# 2016_FDP_SCHEMA.net
KiCad netlist of a schematic drawn in Altium Designer
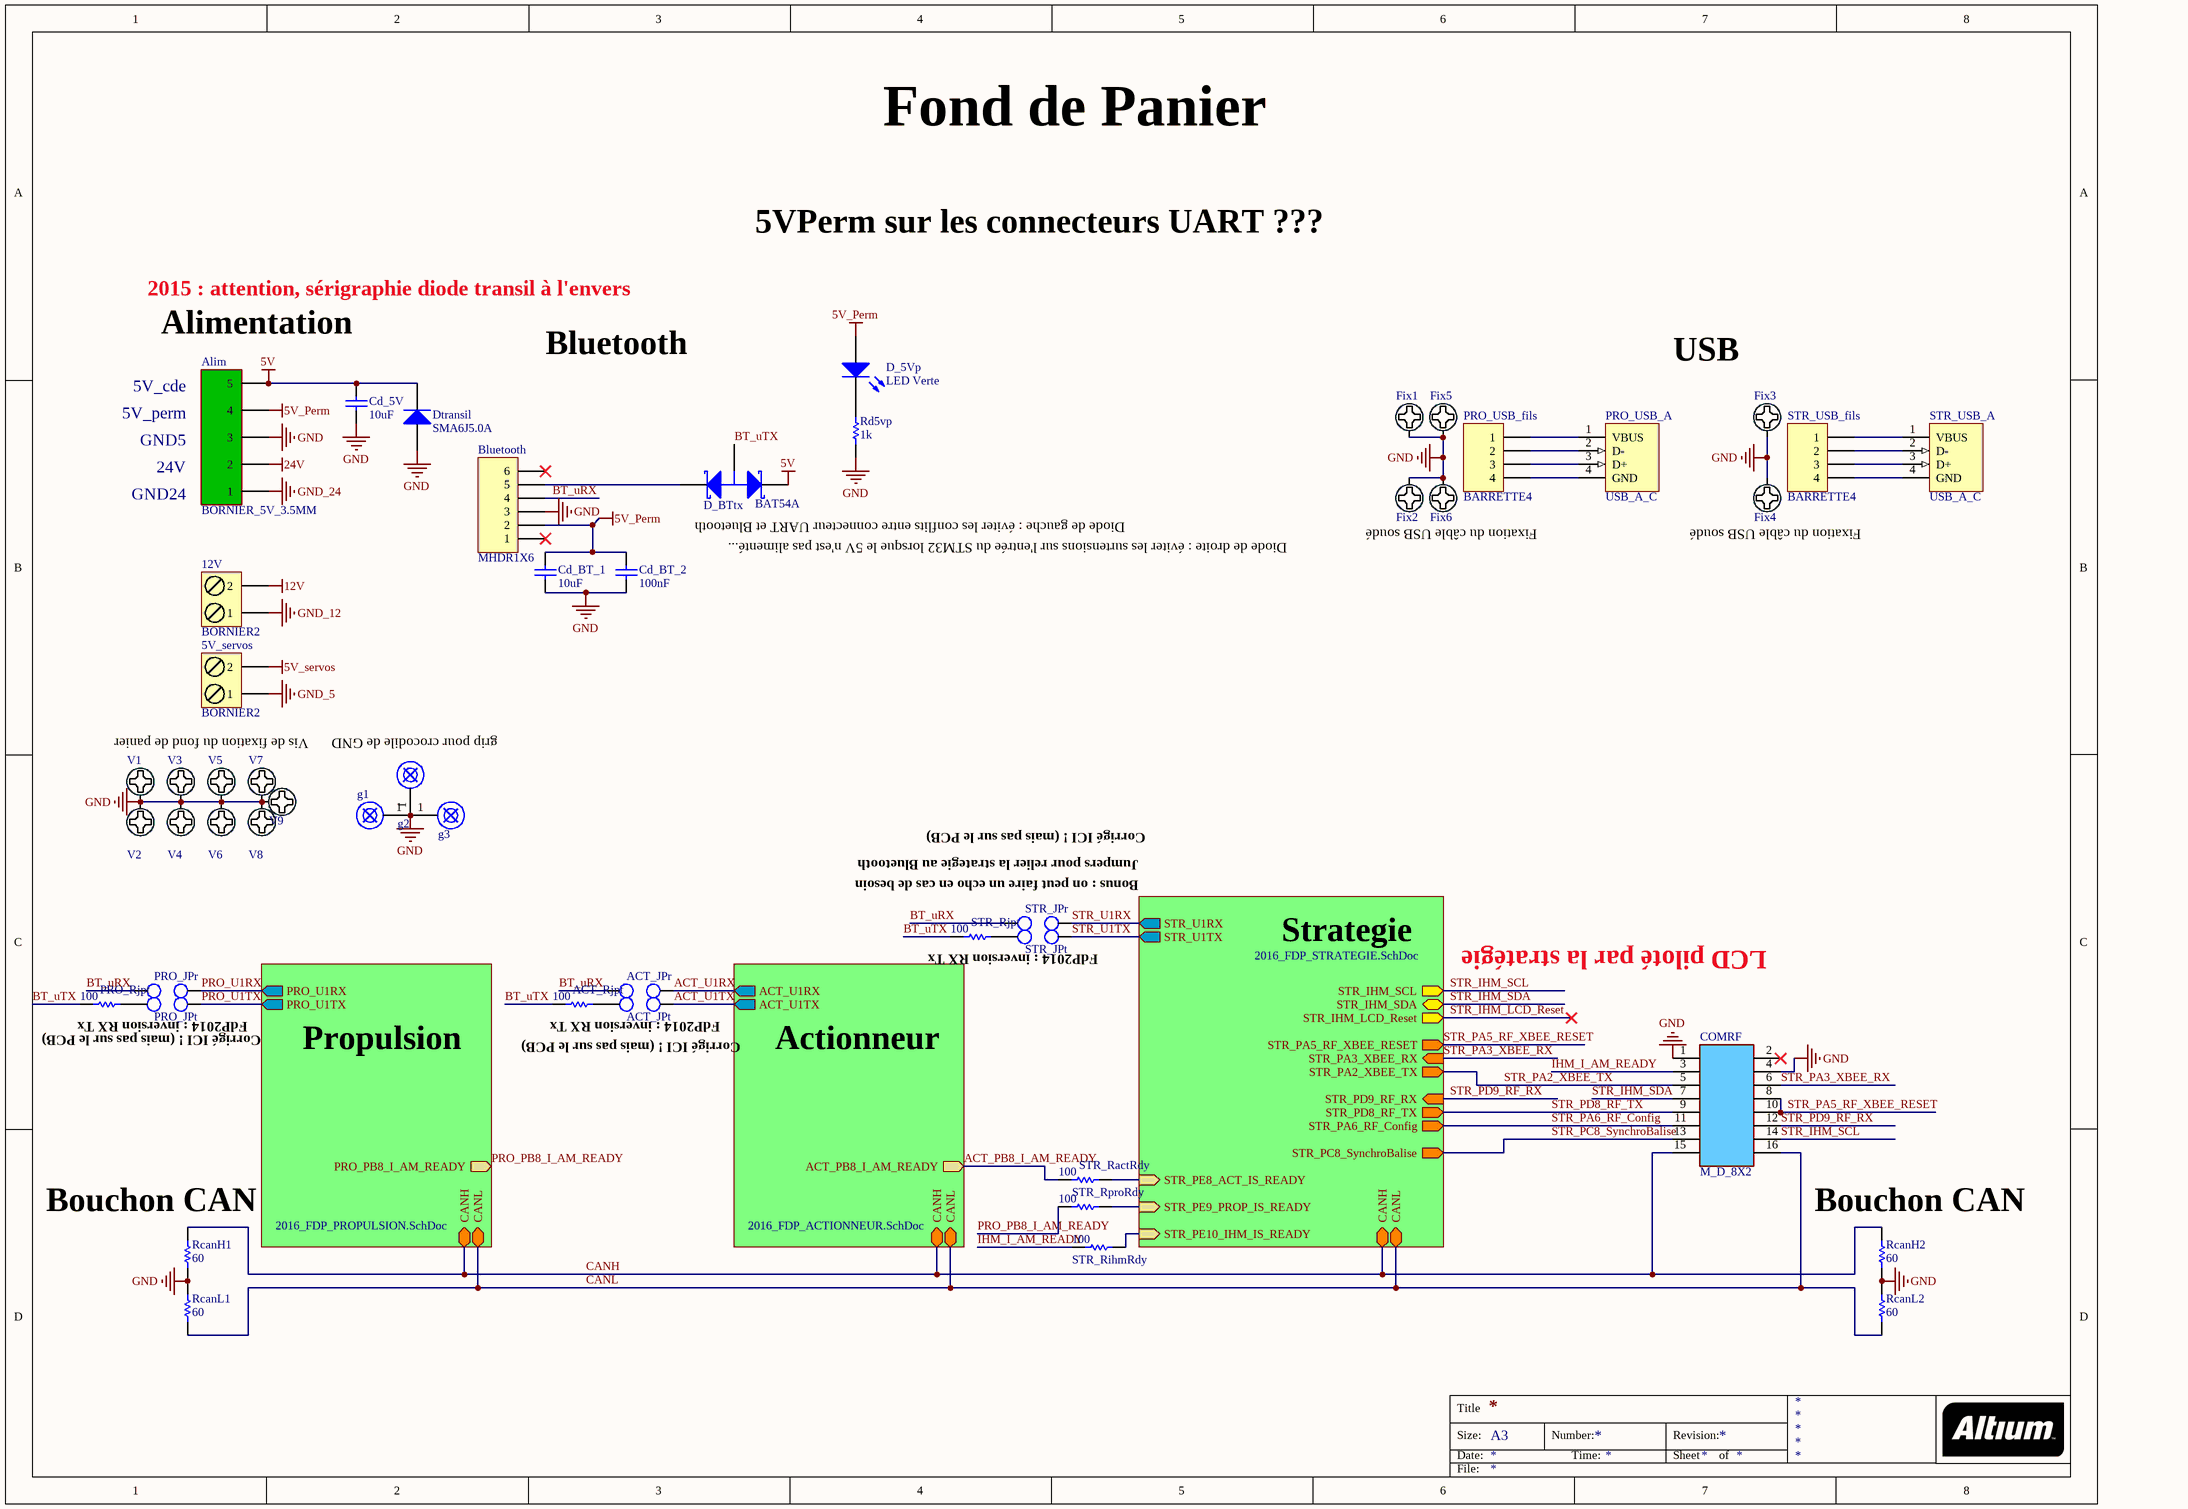
[diagram p0: 2016_FDP_SCHEMA.SchDoc]

(export (version "E")
  (design (tool "Eeschema 10.0.6"))
  (components
    (comp (ref "5V_servos")
      (value "BORNIER2")
      (footprint "BORNIER_2V_5.08MM")
      (description "Terminal blocks, 2 pins, pitch=5mm")
      (libsource (lib "Connecteur") (part "BORNIER2"))
    )
    (comp (ref "12V")
      (value "BORNIER2")
      (footprint "BORNIER_2V_5.08MM")
      (description "Terminal blocks, 2 pins, pitch=5mm")
      (libsource (lib "Connecteur") (part "BORNIER2"))
    )
    (comp (ref "ACT_JPr")
      (value "JUMPER2")
      (footprint "BARRETTE_2_M_D")
      (description "BARRETTE 2 CONTACTS 1 RANGEE MALE DROITE")
      (libsource (lib "connecteurs") (part "JUMPER2"))
    )
    (comp (ref "ACT_JPt")
      (value "JUMPER2")
      (footprint "BARRETTE_2_M_D")
      (description "BARRETTE 2 CONTACTS 1 RANGEE MALE DROITE")
      (libsource (lib "connecteurs") (part "JUMPER2"))
    )
    (comp (ref "ACT_Rjpt")
      (value "100")
      (footprint "R1206_N")
      (description "Resistor")
      (fields (field (name "PUBLISHER") "Altium Limited"))
      (libsource (lib "_ROBOT") (part "Resistor"))
    )
    (comp (ref "Alim")
      (value "BORNIER_5V_3.5MM")
      (footprint "BORNIER_5V_3.5MM_femelle_0")
      (libsource (lib "Connecteur") (part "BORNIER_5V_3.5MM"))
    )
    (comp (ref "Bluetooth")
      (value "MHDR1X6")
      (footprint "HE14_6")
      (description "Header, 6-Pin")
      (fields (field (name "PUBLISHER") "Altium Limited"))
      (libsource (lib "Miscellaneous Connectors") (part "MHDR1X6"))
    )
    (comp (ref "Cd_5V")
      (value "10uF")
      (footprint "C1206_N")
      (description "Capacitor")
      (fields (field (name "PUBLISHER") "Altium Limited"))
      (libsource (lib "_ROBOT") (part "Condensateur"))
    )
    (comp (ref "Cd_BT_1")
      (value "10uF")
      (footprint "C1206_N")
      (description "Capacitor")
      (fields (field (name "PUBLISHER") "Altium Limited"))
      (libsource (lib "_ROBOT") (part "Condensateur"))
    )
    (comp (ref "Cd_BT_2")
      (value "100nF")
      (footprint "C0805_N")
      (description "Capacitor")
      (fields (field (name "PUBLISHER") "Altium Limited"))
      (libsource (lib "_ROBOT") (part "Condensateur"))
    )
    (comp (ref "COMRF")
      (value "BARRETTE_8 CONTACTS_2 RANGEES_MALE_DROITE")
      (footprint "HE10/16_M_D_B P")
      (fields (field (name "TYPE") "M_D_8X2"))
      (libsource (lib "connecteurs") (part "BARRETTE_8 CONTACTS_2 RANGEES_MALE_DROITE"))
    )
    (comp (ref "Dtransil")
      (value "SMA6J5.0A")
      (footprint "DO214AC")
      (description "1 Amp General Purpose Rectifier")
      (fields (field (name "PUBLISHER") "Altium Limited"))
      (libsource (lib "Miscellaneous Devices") (part "Diode 1N4001"))
    )
    (comp (ref "D_5Vp")
      (value "LED Verte")
      (footprint "LED_0805")
      (description "Typical LED")
      (fields (field (name "PUBLISHER") "Altium Limited"))
      (libsource (lib "_ROBOT") (part "LED"))
    )
    (comp (ref "D_BTtx")
      (value "BAT54A")
      (footprint "SOT23-3N")
      (description "DIODE SCHOTTKY DOUBLE")
      (fields (field (name "MANUFACTURER") "ZETEX"))
      (libsource (lib "_ROBOT") (part "Diode Shottky double  BAT54A"))
    )
    (comp (ref "Fix1")
      (value "Pad_M3")
      (footprint "Point Test_D3_P1.6mm")
      (description "Vis M3 X 6mm _TORX_Tête 6mm")
      (fields (field (name "PUBLISHER") "Damien Guitton"))
      (libsource (lib "DG_Mecanique") (part "Vis M3 X 6mm _TORX_Tête 6mm"))
    )
    (comp (ref "Fix2")
      (value "Pad_M3")
      (footprint "Point Test_D3_P1.6mm")
      (description "Vis M3 X 6mm _TORX_Tête 6mm")
      (fields (field (name "PUBLISHER") "Damien Guitton"))
      (libsource (lib "DG_Mecanique") (part "Vis M3 X 6mm _TORX_Tête 6mm"))
    )
    (comp (ref "Fix3")
      (value "Pad_M3")
      (footprint "Point Test_D3_P1.6mm")
      (description "Vis M3 X 6mm _TORX_Tête 6mm")
      (fields (field (name "PUBLISHER") "Damien Guitton"))
      (libsource (lib "DG_Mecanique") (part "Vis M3 X 6mm _TORX_Tête 6mm"))
    )
    (comp (ref "Fix4")
      (value "Pad_M3")
      (footprint "Point Test_D3_P1.6mm")
      (description "Vis M3 X 6mm _TORX_Tête 6mm")
      (fields (field (name "PUBLISHER") "Damien Guitton"))
      (libsource (lib "DG_Mecanique") (part "Vis M3 X 6mm _TORX_Tête 6mm"))
    )
    (comp (ref "Fix5")
      (value "Pad_M3")
      (footprint "Point Test_D3_P1.6mm")
      (description "Vis M3 X 6mm _TORX_Tête 6mm")
      (fields (field (name "PUBLISHER") "Damien Guitton"))
      (libsource (lib "DG_Mecanique") (part "Vis M3 X 6mm _TORX_Tête 6mm"))
    )
    (comp (ref "Fix6")
      (value "Pad_M3")
      (footprint "Point Test_D3_P1.6mm")
      (description "Vis M3 X 6mm _TORX_Tête 6mm")
      (fields (field (name "PUBLISHER") "Damien Guitton"))
      (libsource (lib "DG_Mecanique") (part "Vis M3 X 6mm _TORX_Tête 6mm"))
    )
    (comp (ref "g1")
      (value "grip")
      (footprint "POINT_TEST")
      (description "POINT TEST")
      (libsource (lib "connecteurs") (part "POINT_TEST"))
    )
    (comp (ref "g2")
      (value "grip")
      (footprint "POINT_TEST")
      (description "POINT TEST")
      (libsource (lib "connecteurs") (part "POINT_TEST"))
    )
    (comp (ref "g3")
      (value "grip")
      (footprint "POINT_TEST")
      (description "POINT TEST")
      (libsource (lib "connecteurs") (part "POINT_TEST"))
    )
    (comp (ref "PRO_JPr")
      (value "JUMPER2")
      (footprint "BARRETTE_2_M_D")
      (description "BARRETTE 2 CONTACTS 1 RANGEE MALE DROITE")
      (libsource (lib "connecteurs") (part "JUMPER2"))
    )
    (comp (ref "PRO_JPt")
      (value "JUMPER2")
      (footprint "BARRETTE_2_M_D")
      (description "BARRETTE 2 CONTACTS 1 RANGEE MALE DROITE")
      (libsource (lib "connecteurs") (part "JUMPER2"))
    )
    (comp (ref "PRO_Rjpt")
      (value "100")
      (footprint "R1206_N")
      (description "Resistor")
      (fields (field (name "PUBLISHER") "Altium Limited"))
      (libsource (lib "_ROBOT") (part "Resistor"))
    )
    (comp (ref "PRO_USB_A")
      (value "USB_A_COUDEE")
      (footprint "USB_A_C")
      (description "EMBASE USB TRAVERSANTE TYPE A COUDEE")
      (fields (field (name "TYPE") "USB_A_C"))
      (libsource (lib "connecteurs") (part "USB_A_COUDEE"))
    )
    (comp (ref "PRO_USB_fils")
      (value "BARRETTE4")
      (footprint "HE14_4")
      (description "Header, 4-Pin")
      (fields (field (name "PUBLISHER") "Altium Limited"))
      (libsource (lib "Connecteur") (part "BARRETTE4"))
    )
    (comp (ref "RcanH1")
      (value "60")
      (footprint "R1206_N")
      (description "Resistor")
      (fields (field (name "PUBLISHER") "Altium Limited"))
      (libsource (lib "_ROBOT") (part "Resistor"))
    )
    (comp (ref "RcanH2")
      (value "60")
      (footprint "R1206_N")
      (description "Resistor")
      (fields (field (name "PUBLISHER") "Altium Limited"))
      (libsource (lib "_ROBOT") (part "Resistor"))
    )
    (comp (ref "RcanL1")
      (value "60")
      (footprint "R1206_N")
      (description "Resistor")
      (fields (field (name "PUBLISHER") "Altium Limited"))
      (libsource (lib "_ROBOT") (part "Resistor"))
    )
    (comp (ref "RcanL2")
      (value "60")
      (footprint "R1206_N")
      (description "Resistor")
      (fields (field (name "PUBLISHER") "Altium Limited"))
      (libsource (lib "_ROBOT") (part "Resistor"))
    )
    (comp (ref "Rd5vp")
      (value "1k")
      (footprint "R1206_N")
      (description "Resistor")
      (fields (field (name "PUBLISHER") "Altium Limited"))
      (libsource (lib "_ROBOT") (part "Resistor"))
    )
    (comp (ref "STR_JPr")
      (value "JUMPER2")
      (footprint "BARRETTE_2_M_D")
      (description "BARRETTE 2 CONTACTS 1 RANGEE MALE DROITE")
      (libsource (lib "connecteurs") (part "JUMPER2"))
    )
    (comp (ref "STR_JPt")
      (value "JUMPER2")
      (footprint "BARRETTE_2_M_D")
      (description "BARRETTE 2 CONTACTS 1 RANGEE MALE DROITE")
      (libsource (lib "connecteurs") (part "JUMPER2"))
    )
    (comp (ref "STR_RactRdy")
      (value "100")
      (footprint "R1206_N")
      (description "Resistor")
      (fields (field (name "PUBLISHER") "Altium Limited"))
      (libsource (lib "_ROBOT") (part "Resistor"))
    )
    (comp (ref "STR_RihmRdy")
      (value "100")
      (footprint "R1206_N")
      (description "Resistor")
      (fields (field (name "PUBLISHER") "Altium Limited"))
      (libsource (lib "_ROBOT") (part "Resistor"))
    )
    (comp (ref "STR_Rjpt")
      (value "100")
      (footprint "R1206_N")
      (description "Resistor")
      (fields (field (name "PUBLISHER") "Altium Limited"))
      (libsource (lib "_ROBOT") (part "Resistor"))
    )
    (comp (ref "STR_RproRdy")
      (value "100")
      (footprint "R1206_N")
      (description "Resistor")
      (fields (field (name "PUBLISHER") "Altium Limited"))
      (libsource (lib "_ROBOT") (part "Resistor"))
    )
    (comp (ref "STR_USB_A")
      (value "USB_A_COUDEE")
      (footprint "USB_A_C")
      (description "EMBASE USB TRAVERSANTE TYPE A COUDEE")
      (fields (field (name "TYPE") "USB_A_C"))
      (libsource (lib "connecteurs") (part "USB_A_COUDEE"))
    )
    (comp (ref "STR_USB_fils")
      (value "BARRETTE4")
      (footprint "HE14_4")
      (description "Header, 4-Pin")
      (fields (field (name "PUBLISHER") "Altium Limited"))
      (libsource (lib "Connecteur") (part "BARRETTE4"))
    )
    (comp (ref "V1")
      (value "Pad_M3")
      (footprint "M3x6mm Torx")
      (description "Vis M3 X 6mm _TORX_Tête 6mm")
      (fields (field (name "PUBLISHER") "Damien Guitton"))
      (libsource (lib "DG_Mecanique") (part "Vis M3 X 6mm _TORX_Tête 6mm"))
    )
    (comp (ref "V2")
      (value "Pad_M3")
      (footprint "M3x6mm Torx")
      (description "Vis M3 X 6mm _TORX_Tête 6mm")
      (fields (field (name "PUBLISHER") "Damien Guitton"))
      (libsource (lib "DG_Mecanique") (part "Vis M3 X 6mm _TORX_Tête 6mm"))
    )
    (comp (ref "V3")
      (value "Pad_M3")
      (footprint "M3x6mm Torx")
      (description "Vis M3 X 6mm _TORX_Tête 6mm")
      (fields (field (name "PUBLISHER") "Damien Guitton"))
      (libsource (lib "DG_Mecanique") (part "Vis M3 X 6mm _TORX_Tête 6mm"))
    )
    (comp (ref "V4")
      (value "Pad_M3")
      (footprint "M3x6mm Torx")
      (description "Vis M3 X 6mm _TORX_Tête 6mm")
      (fields (field (name "PUBLISHER") "Damien Guitton"))
      (libsource (lib "DG_Mecanique") (part "Vis M3 X 6mm _TORX_Tête 6mm"))
    )
    (comp (ref "V5")
      (value "Pad_M3")
      (footprint "M3x6mm Torx")
      (description "Vis M3 X 6mm _TORX_Tête 6mm")
      (fields (field (name "PUBLISHER") "Damien Guitton"))
      (libsource (lib "DG_Mecanique") (part "Vis M3 X 6mm _TORX_Tête 6mm"))
    )
    (comp (ref "V6")
      (value "Pad_M3")
      (footprint "M3x6mm Torx")
      (description "Vis M3 X 6mm _TORX_Tête 6mm")
      (fields (field (name "PUBLISHER") "Damien Guitton"))
      (libsource (lib "DG_Mecanique") (part "Vis M3 X 6mm _TORX_Tête 6mm"))
    )
    (comp (ref "V7")
      (value "Pad_M3")
      (footprint "M3x6mm Torx")
      (description "Vis M3 X 6mm _TORX_Tête 6mm")
      (fields (field (name "PUBLISHER") "Damien Guitton"))
      (libsource (lib "DG_Mecanique") (part "Vis M3 X 6mm _TORX_Tête 6mm"))
    )
    (comp (ref "V8")
      (value "Pad_M3")
      (footprint "M3x6mm Torx")
      (description "Vis M3 X 6mm _TORX_Tête 6mm")
      (fields (field (name "PUBLISHER") "Damien Guitton"))
      (libsource (lib "DG_Mecanique") (part "Vis M3 X 6mm _TORX_Tête 6mm"))
    )
    (comp (ref "V9")
      (value "Pad_M3")
      (footprint "M3x6mm Torx")
      (description "Vis M3 X 6mm _TORX_Tête 6mm")
      (fields (field (name "PUBLISHER") "Damien Guitton"))
      (libsource (lib "DG_Mecanique") (part "Vis M3 X 6mm _TORX_Tête 6mm"))
    )
  )
  (nets
    (net (code "1") (name "/ACT_PB8_I_AM_READY") (class "Default")
      (node (ref "STR_RactRdy") (pin "2") (pinfunction "2_2") (pintype "passive"))
    )
    (net (code "2") (name "/ACT_U1RX") (class "Default")
      (node (ref "ACT_JPr") (pin "2") (pinfunction "2_2") (pintype "passive"))
    )
    (net (code "3") (name "/ACT_U1TX") (class "Default")
      (node (ref "ACT_JPt") (pin "2") (pinfunction "2_2") (pintype "passive"))
    )
    (net (code "4") (name "/BT_uRX") (class "Default")
      (node (ref "ACT_JPr") (pin "1") (pinfunction "1_1") (pintype "passive"))
      (node (ref "Bluetooth") (pin "4") (pinfunction "4_4") (pintype "passive"))
      (node (ref "PRO_JPr") (pin "1") (pinfunction "1_1") (pintype "passive"))
      (node (ref "STR_JPr") (pin "1") (pinfunction "1_1") (pintype "passive"))
    )
    (net (code "5") (name "/BT_uTX") (class "Default")
      (node (ref "ACT_Rjpt") (pin "2") (pinfunction "2_2") (pintype "passive"))
      (node (ref "D_BTtx") (pin "3") (pinfunction "A_3") (pintype "passive"))
      (node (ref "PRO_Rjpt") (pin "2") (pinfunction "2_2") (pintype "passive"))
      (node (ref "STR_Rjpt") (pin "2") (pinfunction "2_2") (pintype "passive"))
    )
    (net (code "6") (name "/CANH") (class "Default")
      (node (ref "COMRF") (pin "15") (pinfunction "15_15") (pintype "passive"))
      (node (ref "RcanH1") (pin "2") (pinfunction "2_2") (pintype "passive"))
      (node (ref "RcanH2") (pin "1") (pinfunction "1_1") (pintype "passive"))
    )
    (net (code "7") (name "/CANL") (class "Default")
      (node (ref "COMRF") (pin "16") (pinfunction "16_16") (pintype "passive"))
      (node (ref "RcanL1") (pin "1") (pinfunction "1_1") (pintype "passive"))
      (node (ref "RcanL2") (pin "1") (pinfunction "1_1") (pintype "passive"))
    )
    (net (code "8") (name "/IHM_I_AM_READY") (class "Default")
      (node (ref "COMRF") (pin "3") (pinfunction "3_3") (pintype "passive"))
      (node (ref "STR_RihmRdy") (pin "2") (pinfunction "2_2") (pintype "passive"))
    )
    (net (code "9") (name "/PRO_PB8_I_AM_READY") (class "Default")
      (node (ref "STR_RproRdy") (pin "2") (pinfunction "2_2") (pintype "passive"))
    )
    (net (code "10") (name "/PRO_U1RX") (class "Default")
      (node (ref "PRO_JPr") (pin "2") (pinfunction "2_2") (pintype "passive"))
    )
    (net (code "11") (name "/PRO_U1TX") (class "Default")
      (node (ref "PRO_JPt") (pin "2") (pinfunction "2_2") (pintype "passive"))
    )
    (net (code "13") (name "/STR_IHM_SCL") (class "Default")
      (node (ref "COMRF") (pin "14") (pinfunction "14_14") (pintype "passive"))
    )
    (net (code "14") (name "/STR_IHM_SDA") (class "Default")
      (node (ref "COMRF") (pin "7") (pinfunction "7_7") (pintype "passive"))
    )
    (net (code "15") (name "/STR_PA2_XBEE_TX") (class "Default")
      (node (ref "COMRF") (pin "5") (pinfunction "5_5") (pintype "passive"))
    )
    (net (code "16") (name "/STR_PA3_XBEE_RX") (class "Default")
      (node (ref "COMRF") (pin "6") (pinfunction "6_6") (pintype "passive"))
    )
    (net (code "17") (name "/STR_PA5_RF_XBEE_RESET") (class "Default")
      (node (ref "COMRF") (pin "10") (pinfunction "10_10") (pintype "passive"))
      (node (ref "COMRF") (pin "8") (pinfunction "8_8") (pintype "passive"))
    )
    (net (code "18") (name "/STR_PA6_RF_Config") (class "Default")
      (node (ref "COMRF") (pin "11") (pinfunction "11_11") (pintype "passive"))
    )
    (net (code "19") (name "/STR_PC8_SynchroBalise") (class "Default")
      (node (ref "COMRF") (pin "13") (pinfunction "13_13") (pintype "passive"))
    )
    (net (code "20") (name "/STR_PD8_RF_TX") (class "Default")
      (node (ref "COMRF") (pin "9") (pinfunction "9_9") (pintype "passive"))
    )
    (net (code "21") (name "/STR_PD9_RF_RX") (class "Default")
      (node (ref "COMRF") (pin "12") (pinfunction "12_12") (pintype "passive"))
    )
    (net (code "22") (name "/STR_PE8_ACT_IS_READY") (class "Default")
      (node (ref "STR_RactRdy") (pin "1") (pinfunction "1_1") (pintype "passive"))
    )
    (net (code "23") (name "/STR_PE9_PROP_IS_READY") (class "Default")
      (node (ref "STR_RproRdy") (pin "1") (pinfunction "1_1") (pintype "passive"))
    )
    (net (code "24") (name "/STR_PE10_IHM_IS_READY") (class "Default")
      (node (ref "STR_RihmRdy") (pin "1") (pinfunction "1_1") (pintype "passive"))
    )
    (net (code "25") (name "/STR_U1RX") (class "Default")
      (node (ref "STR_JPr") (pin "2") (pinfunction "2_2") (pintype "passive"))
    )
    (net (code "26") (name "/STR_U1TX") (class "Default")
      (node (ref "STR_JPt") (pin "2") (pinfunction "2_2") (pintype "passive"))
    )
    (net (code "27") (name "5V") (class "Default")
      (node (ref "Alim") (pin "5") (pinfunction "5_5") (pintype "passive"))
      (node (ref "Cd_5V") (pin "2") (pinfunction "2_2") (pintype "passive"))
      (node (ref "D_BTtx") (pin "2") (pinfunction "K2_2") (pintype "passive"))
      (node (ref "Dtransil") (pin "2") (pinfunction "K_2") (pintype "passive"))
    )
    (net (code "28") (name "5V_Perm") (class "Default")
      (node (ref "Alim") (pin "4") (pinfunction "4_4") (pintype "passive"))
      (node (ref "Bluetooth") (pin "2") (pinfunction "2_2") (pintype "passive"))
      (node (ref "Cd_BT_1") (pin "2") (pinfunction "2_2") (pintype "passive"))
      (node (ref "Cd_BT_2") (pin "2") (pinfunction "2_2") (pintype "passive"))
      (node (ref "D_5Vp") (pin "1") (pinfunction "A_1") (pintype "passive"))
    )
    (net (code "29") (name "5V_servos") (class "Default")
      (node (ref "5V_servos") (pin "2") (pinfunction "2_2") (pintype "passive"))
    )
    (net (code "30") (name "12V") (class "Default")
      (node (ref "12V") (pin "2") (pinfunction "2_2") (pintype "passive"))
    )
    (net (code "31") (name "24V") (class "Default")
      (node (ref "Alim") (pin "2") (pinfunction "2_2") (pintype "passive"))
    )
    (net (code "32") (name "GND") (class "Default")
      (node (ref "Alim") (pin "3") (pinfunction "3_3") (pintype "passive"))
      (node (ref "Bluetooth") (pin "3") (pinfunction "3_3") (pintype "passive"))
      (node (ref "COMRF") (pin "1") (pinfunction "1_1") (pintype "passive"))
      (node (ref "COMRF") (pin "4") (pinfunction "4_4") (pintype "passive"))
      (node (ref "Cd_5V") (pin "1") (pinfunction "1_1") (pintype "passive"))
      (node (ref "Cd_BT_1") (pin "1") (pinfunction "1_1") (pintype "passive"))
      (node (ref "Cd_BT_2") (pin "1") (pinfunction "1_1") (pintype "passive"))
      (node (ref "Dtransil") (pin "1") (pinfunction "A_1") (pintype "passive"))
      (node (ref "Fix1") (pin "1") (pinfunction "1_1") (pintype "passive"))
      (node (ref "Fix2") (pin "1") (pinfunction "1_1") (pintype "passive"))
      (node (ref "Fix3") (pin "1") (pinfunction "1_1") (pintype "passive"))
      (node (ref "Fix4") (pin "1") (pinfunction "1_1") (pintype "passive"))
      (node (ref "Fix5") (pin "1") (pinfunction "1_1") (pintype "passive"))
      (node (ref "Fix6") (pin "1") (pinfunction "1_1") (pintype "passive"))
      (node (ref "RcanH1") (pin "1") (pinfunction "1_1") (pintype "passive"))
      (node (ref "RcanH2") (pin "2") (pinfunction "2_2") (pintype "passive"))
      (node (ref "RcanL1") (pin "2") (pinfunction "2_2") (pintype "passive"))
      (node (ref "RcanL2") (pin "2") (pinfunction "2_2") (pintype "passive"))
      (node (ref "Rd5vp") (pin "2") (pinfunction "2_2") (pintype "passive"))
      (node (ref "V1") (pin "1") (pinfunction "1_1") (pintype "passive"))
      (node (ref "V2") (pin "1") (pinfunction "1_1") (pintype "passive"))
      (node (ref "V3") (pin "1") (pinfunction "1_1") (pintype "passive"))
      (node (ref "V4") (pin "1") (pinfunction "1_1") (pintype "passive"))
      (node (ref "V5") (pin "1") (pinfunction "1_1") (pintype "passive"))
      (node (ref "V6") (pin "1") (pinfunction "1_1") (pintype "passive"))
      (node (ref "V7") (pin "1") (pinfunction "1_1") (pintype "passive"))
      (node (ref "V8") (pin "1") (pinfunction "1_1") (pintype "passive"))
      (node (ref "V9") (pin "1") (pinfunction "1_1") (pintype "passive"))
      (node (ref "g1") (pin "1") (pinfunction "3_1") (pintype "passive"))
      (node (ref "g2") (pin "1") (pinfunction "3_1") (pintype "passive"))
      (node (ref "g3") (pin "1") (pinfunction "3_1") (pintype "passive"))
    )
    (net (code "33") (name "GND_5") (class "Default")
      (node (ref "5V_servos") (pin "1") (pinfunction "1_1") (pintype "passive"))
    )
    (net (code "34") (name "GND_12") (class "Default")
      (node (ref "12V") (pin "1") (pinfunction "1_1") (pintype "passive"))
    )
    (net (code "35") (name "GND_24") (class "Default")
      (node (ref "Alim") (pin "1") (pinfunction "1_1") (pintype "passive"))
    )
    (net (code "36") (name "Net-(ACT_JPt-Pad1)") (class "Default")
      (node (ref "ACT_JPt") (pin "1") (pinfunction "1_1") (pintype "passive"))
      (node (ref "ACT_Rjpt") (pin "1") (pinfunction "1_1") (pintype "passive"))
    )
    (net (code "37") (name "Net-(D_5Vp-K)") (class "Default")
      (node (ref "D_5Vp") (pin "2") (pinfunction "K_2") (pintype "passive"))
      (node (ref "Rd5vp") (pin "1") (pinfunction "1_1") (pintype "passive"))
    )
    (net (code "38") (name "Net-(D_BTtx-K1)") (class "Default")
      (node (ref "Bluetooth") (pin "5") (pinfunction "5_5") (pintype "passive"))
      (node (ref "D_BTtx") (pin "1") (pinfunction "K1_1") (pintype "passive"))
    )
    (net (code "39") (name "Net-(PRO_JPt-Pad1)") (class "Default")
      (node (ref "PRO_JPt") (pin "1") (pinfunction "1_1") (pintype "passive"))
      (node (ref "PRO_Rjpt") (pin "1") (pinfunction "1_1") (pintype "passive"))
    )
    (net (code "40") (name "Net-(PRO_USB_A-D+)") (class "Default")
      (node (ref "PRO_USB_A") (pin "3") (pinfunction "D+_3") (pintype "input"))
      (node (ref "PRO_USB_fils") (pin "3") (pinfunction "3_3") (pintype "passive"))
    )
    (net (code "41") (name "Net-(PRO_USB_A-D-)") (class "Default")
      (node (ref "PRO_USB_A") (pin "2") (pinfunction "D-_2") (pintype "input"))
      (node (ref "PRO_USB_fils") (pin "2") (pinfunction "2_2") (pintype "passive"))
    )
    (net (code "42") (name "Net-(PRO_USB_A-GND)") (class "Default")
      (node (ref "PRO_USB_A") (pin "4") (pinfunction "GND_4") (pintype "power_in"))
      (node (ref "PRO_USB_fils") (pin "4") (pinfunction "4_4") (pintype "passive"))
    )
    (net (code "43") (name "Net-(PRO_USB_A-VBUS)") (class "Default")
      (node (ref "PRO_USB_A") (pin "1") (pinfunction "VBUS_1") (pintype "power_in"))
      (node (ref "PRO_USB_fils") (pin "1") (pinfunction "1_1") (pintype "passive"))
    )
    (net (code "44") (name "Net-(STR_JPt-Pad1)") (class "Default")
      (node (ref "STR_JPt") (pin "1") (pinfunction "1_1") (pintype "passive"))
      (node (ref "STR_Rjpt") (pin "1") (pinfunction "1_1") (pintype "passive"))
    )
    (net (code "45") (name "Net-(STR_USB_A-D+)") (class "Default")
      (node (ref "STR_USB_A") (pin "3") (pinfunction "D+_3") (pintype "input"))
      (node (ref "STR_USB_fils") (pin "3") (pinfunction "3_3") (pintype "passive"))
    )
    (net (code "46") (name "Net-(STR_USB_A-D-)") (class "Default")
      (node (ref "STR_USB_A") (pin "2") (pinfunction "D-_2") (pintype "input"))
      (node (ref "STR_USB_fils") (pin "2") (pinfunction "2_2") (pintype "passive"))
    )
    (net (code "47") (name "Net-(STR_USB_A-GND)") (class "Default")
      (node (ref "STR_USB_A") (pin "4") (pinfunction "GND_4") (pintype "power_in"))
      (node (ref "STR_USB_fils") (pin "4") (pinfunction "4_4") (pintype "passive"))
    )
    (net (code "48") (name "Net-(STR_USB_A-VBUS)") (class "Default")
      (node (ref "STR_USB_A") (pin "1") (pinfunction "VBUS_1") (pintype "power_in"))
      (node (ref "STR_USB_fils") (pin "1") (pinfunction "1_1") (pintype "passive"))
    )
    (net (code "49") (name "unconnected-(Bluetooth-Pad1)") (class "Default")
      (node (ref "Bluetooth") (pin "1") (pinfunction "1_1") (pintype "passive+no_connect"))
    )
    (net (code "50") (name "unconnected-(Bluetooth-Pad6)") (class "Default")
      (node (ref "Bluetooth") (pin "6") (pinfunction "6_6") (pintype "passive+no_connect"))
    )
    (net (code "51") (name "unconnected-(COMRF-Pad2)") (class "Default")
      (node (ref "COMRF") (pin "2") (pinfunction "2_2") (pintype "passive+no_connect"))
    )
  )
)
